# untitled.net
KiCad netlist of a schematic drawn in EAGLE
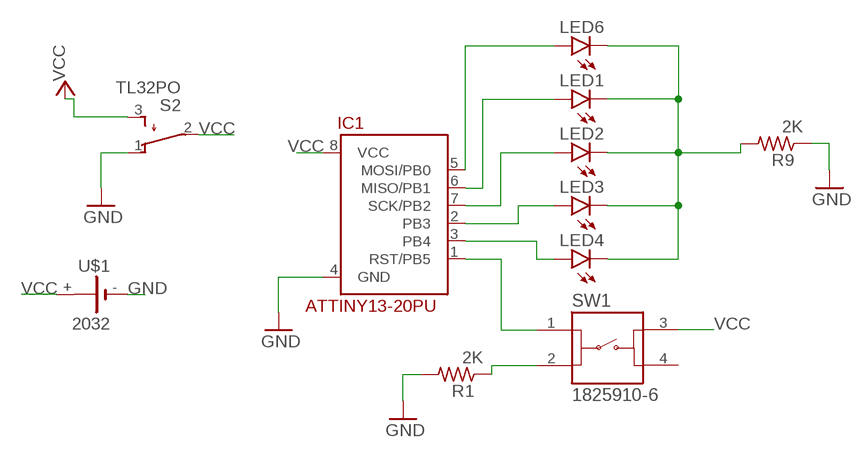
[diagram p0: schematic, sheet 1]

(export (version "E")
  (design (tool "Eeschema 10.0.6"))
  (components
    (comp (ref "IC1")
      (value "ATTINY13-20PU")
      (footprint "eagle-import:DIL08")
      (libsource (lib "eagle-import") (part "ATTINY13-20PU"))
    )
    (comp (ref "LED1")
      (value "LED3MM")
      (footprint "eagle-import:LED3MM")
      (libsource (lib "eagle-import") (part "LED3MM"))
    )
    (comp (ref "LED2")
      (value "LED3MM")
      (footprint "eagle-import:LED3MM")
      (libsource (lib "eagle-import") (part "LED3MM"))
    )
    (comp (ref "LED3")
      (value "LED3MM")
      (footprint "eagle-import:LED3MM")
      (libsource (lib "eagle-import") (part "LED3MM"))
    )
    (comp (ref "LED4")
      (value "LED3MM")
      (footprint "eagle-import:LED3MM")
      (libsource (lib "eagle-import") (part "LED3MM"))
    )
    (comp (ref "LED6")
      (value "LED3MM")
      (footprint "eagle-import:LED3MM")
      (libsource (lib "eagle-import") (part "LED3MM"))
    )
    (comp (ref "R1")
      (value "2K")
      (footprint "eagle-import:0204_7")
      (libsource (lib "eagle-import") (part "R-US_0204/7"))
    )
    (comp (ref "R9")
      (value "2K")
      (footprint "eagle-import:0204_7")
      (libsource (lib "eagle-import") (part "R-US_0204/7"))
    )
    (comp (ref "S2")
      (value "TL32PO")
      (footprint "eagle-import:TL3XPO")
      (libsource (lib "eagle-import") (part "TL32PO"))
    )
    (comp (ref "SW1")
      (value "1825910-6")
      (footprint "eagle-import:1825910-6")
      (fields
        (field (name "DIGIKEY_PART_NUMBER") "450-1650-ND")
        (field (name "MANUFACTURER") "TE Connectivity ALCOSWITCH Switches")
        (field (name "CREATED_BY") " PCBLayout.com")
      )
      (libsource (lib "eagle-import") (part "1825910-6"))
    )
    (comp (ref "U$1")
      (value "2032")
      (footprint "eagle-import:KZH20SMD")
      (libsource (lib "eagle-import") (part "2032"))
    )
  )
  (nets
    (net (code "1") (name "GND") (class "Default")
      (node (ref "IC1") (pin "4") (pinfunction "GND_4") (pintype "power_in"))
      (node (ref "R1") (pin "2") (pinfunction "2_2") (pintype "passive"))
      (node (ref "R9") (pin "1") (pinfunction "1_1") (pintype "passive"))
      (node (ref "S2") (pin "1") (pinfunction "O_1") (pintype "passive"))
      (node (ref "U$1") (pin "-") (pinfunction "-_-") (pintype "passive"))
    )
    (net (code "2") (name "Net-(IC1-MISO{slash}PB1)") (class "Default")
      (node (ref "IC1") (pin "6") (pinfunction "MISO/PB1_6") (pintype "bidirectional"))
      (node (ref "LED1") (pin "A") (pinfunction "A_A") (pintype "passive"))
    )
    (net (code "3") (name "Net-(IC1-MOSI{slash}PB0)") (class "Default")
      (node (ref "IC1") (pin "5") (pinfunction "MOSI/PB0_5") (pintype "bidirectional"))
      (node (ref "LED6") (pin "A") (pinfunction "A_A") (pintype "passive"))
    )
    (net (code "4") (name "Net-(IC1-PB3)") (class "Default")
      (node (ref "IC1") (pin "2") (pinfunction "PB3_2") (pintype "bidirectional"))
      (node (ref "LED3") (pin "A") (pinfunction "A_A") (pintype "passive"))
    )
    (net (code "5") (name "Net-(IC1-PB4)") (class "Default")
      (node (ref "IC1") (pin "3") (pinfunction "PB4_3") (pintype "bidirectional"))
      (node (ref "LED4") (pin "A") (pinfunction "A_A") (pintype "passive"))
    )
    (net (code "6") (name "Net-(IC1-RST{slash}PB5)") (class "Default")
      (node (ref "IC1") (pin "1") (pinfunction "RST/PB5_1") (pintype "bidirectional"))
      (node (ref "SW1") (pin "1") (pinfunction "1_1") (pintype "passive"))
    )
    (net (code "7") (name "Net-(IC1-SCK{slash}PB2)") (class "Default")
      (node (ref "IC1") (pin "7") (pinfunction "SCK/PB2_7") (pintype "bidirectional"))
      (node (ref "LED2") (pin "A") (pinfunction "A_A") (pintype "passive"))
    )
    (net (code "8") (name "Net-(LED1-C)") (class "Default")
      (node (ref "LED1") (pin "K") (pinfunction "C_K") (pintype "passive"))
      (node (ref "LED2") (pin "K") (pinfunction "C_K") (pintype "passive"))
      (node (ref "LED3") (pin "K") (pinfunction "C_K") (pintype "passive"))
      (node (ref "LED4") (pin "K") (pinfunction "C_K") (pintype "passive"))
      (node (ref "LED6") (pin "K") (pinfunction "C_K") (pintype "passive"))
      (node (ref "R9") (pin "2") (pinfunction "2_2") (pintype "passive"))
    )
    (net (code "9") (name "Net-(R1-Pad1)") (class "Default")
      (node (ref "R1") (pin "1") (pinfunction "1_1") (pintype "passive"))
      (node (ref "SW1") (pin "2") (pinfunction "2_2") (pintype "passive"))
    )
    (net (code "10") (name "VCC") (class "Default")
      (node (ref "IC1") (pin "8") (pinfunction "VCC_8") (pintype "power_in"))
      (node (ref "S2") (pin "2") (pinfunction "P_2") (pintype "passive"))
      (node (ref "S2") (pin "3") (pinfunction "S_3") (pintype "passive"))
      (node (ref "SW1") (pin "3") (pinfunction "3_3") (pintype "passive"))
      (node (ref "U$1") (pin "+") (pinfunction "+_+") (pintype "passive"))
    )
    (net (code "11") (name "unconnected-(SW1-Pad4)") (class "Default")
      (node (ref "SW1") (pin "4") (pinfunction "4_4") (pintype "passive"))
    )
  )
)
